# LiPo_Charger.net
KiCad netlist of a schematic drawn in Altium Designer
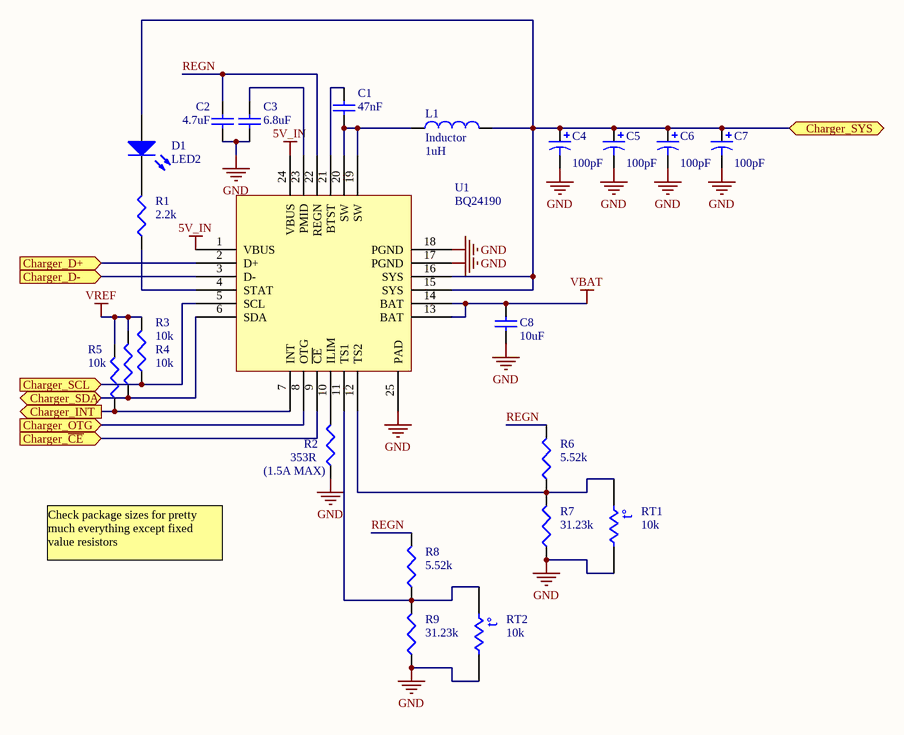
[diagram p0: LiPo_Charger.SchDoc]

(export (version "E")
  (design (tool "Eeschema 10.0.6"))
  (components
    (comp (ref "C1")
      (value "47nF")
      (footprint "1608[0603]")
      (description "Capacitor (Semiconductor SIM Model)")
      (fields (field (name "Comment") "Cap Semi") (field (name "PUBLISHER") "Altium Limited"))
      (libsource (lib "Miscellaneous Devices") (part "Cap Semi"))
    )
    (comp (ref "C2")
      (value "4.7uF")
      (footprint "1608[0603]")
      (description "Capacitor (Semiconductor SIM Model)")
      (fields (field (name "Comment") "Cap Semi") (field (name "PUBLISHER") "Altium Limited"))
      (libsource (lib "Miscellaneous Devices") (part "Cap Semi"))
    )
    (comp (ref "C3")
      (value "6.8uF")
      (footprint "1608[0603]")
      (description "Capacitor (Semiconductor SIM Model)")
      (fields (field (name "Comment") "Cap Semi") (field (name "PUBLISHER") "Altium Limited"))
      (libsource (lib "Miscellaneous Devices") (part "Cap Semi"))
    )
    (comp (ref "C4")
      (value "100pF")
      (footprint "C0805")
      (description "Polarized Capacitor (Surface Mount)")
      (fields (field (name "Comment") "Cap Pol3") (field (name "PUBLISHER") "Altium Limited"))
      (libsource (lib "Miscellaneous Devices") (part "Cap Pol3"))
    )
    (comp (ref "C5")
      (value "100pF")
      (footprint "C0805")
      (description "Polarized Capacitor (Surface Mount)")
      (fields (field (name "Comment") "Cap Pol3") (field (name "PUBLISHER") "Altium Limited"))
      (libsource (lib "Miscellaneous Devices") (part "Cap Pol3"))
    )
    (comp (ref "C6")
      (value "100pF")
      (footprint "C0805")
      (description "Polarized Capacitor (Surface Mount)")
      (fields (field (name "Comment") "Cap Pol3") (field (name "PUBLISHER") "Altium Limited"))
      (libsource (lib "Miscellaneous Devices") (part "Cap Pol3"))
    )
    (comp (ref "C7")
      (value "100pF")
      (footprint "C0805")
      (description "Polarized Capacitor (Surface Mount)")
      (fields (field (name "Comment") "Cap Pol3") (field (name "PUBLISHER") "Altium Limited"))
      (libsource (lib "Miscellaneous Devices") (part "Cap Pol3"))
    )
    (comp (ref "C8")
      (value "10uF")
      (footprint "1608[0603]")
      (description "Capacitor (Semiconductor SIM Model)")
      (fields (field (name "Comment") "Cap Semi") (field (name "PUBLISHER") "Altium Limited"))
      (libsource (lib "Miscellaneous Devices") (part "Cap Semi"))
    )
    (comp (ref "D1")
      (value "LED2")
      (footprint "3.2X1.6X1.1")
      (description "Typical RED, GREEN, YELLOW, AMBER GaAs LED")
      (fields (field (name "PUBLISHER") "Altium Limited"))
      (libsource (lib "Miscellaneous Devices") (part "LED2"))
    )
    (comp (ref "L1")
      (value "Inductor")
      (footprint "0603")
      (fields (field (name "ALTIUM_VALUE") "1uH") (field (name "PUBLISHER") "Altium Limited"))
      (libsource (lib "Miscellaneous Devices") (part "Inductor"))
    )
    (comp (ref "R1")
      (value "2.2k")
      (footprint "J1-0603")
      (description "Resistor")
      (fields (field (name "Comment") "Res3") (field (name "PUBLISHER") "Altium Limited"))
      (libsource (lib "Miscellaneous Devices") (part "Res3"))
    )
    (comp (ref "R2")
      (value "(1.5A MAX)")
      (footprint "J1-0603")
      (description "Resistor")
      (fields (field (name "ALTIUM_VALUE") "353R") (field (name "PUBLISHER") "Altium Limited"))
      (libsource (lib "Miscellaneous Devices") (part "Res3"))
    )
    (comp (ref "R3")
      (value "10k")
      (footprint "J1-0603")
      (description "Resistor")
      (fields (field (name "PUBLISHER") "Altium Limited"))
      (libsource (lib "Miscellaneous Devices") (part "Res3"))
    )
    (comp (ref "R4")
      (value "10k")
      (footprint "J1-0603")
      (description "Resistor")
      (fields (field (name "PUBLISHER") "Altium Limited"))
      (libsource (lib "Miscellaneous Devices") (part "Res3"))
    )
    (comp (ref "R5")
      (value "10k")
      (footprint "J1-0603")
      (description "Resistor")
      (fields (field (name "PUBLISHER") "Altium Limited"))
      (libsource (lib "Miscellaneous Devices") (part "Res3"))
    )
    (comp (ref "R6")
      (value "5.52k")
      (footprint "J1-0603")
      (description "Resistor")
      (fields (field (name "Comment") "Res3") (field (name "PUBLISHER") "Altium Limited"))
      (libsource (lib "Miscellaneous Devices") (part "Res3"))
    )
    (comp (ref "R7")
      (value "31.23k")
      (footprint "J1-0603")
      (description "Resistor")
      (fields (field (name "Comment") "Res3") (field (name "PUBLISHER") "Altium Limited"))
      (libsource (lib "Miscellaneous Devices") (part "Res3"))
    )
    (comp (ref "R8")
      (value "5.52k")
      (footprint "J1-0603")
      (description "Resistor")
      (fields (field (name "Comment") "Res3") (field (name "PUBLISHER") "Altium Limited"))
      (libsource (lib "Miscellaneous Devices") (part "Res3"))
    )
    (comp (ref "R9")
      (value "31.23k")
      (footprint "J1-0603")
      (description "Resistor")
      (fields (field (name "Comment") "Res3") (field (name "PUBLISHER") "Altium Limited"))
      (libsource (lib "Miscellaneous Devices") (part "Res3"))
    )
    (comp (ref "RT1")
      (value "10k")
      (footprint "6-0805_N")
      (description "Thermistor")
      (fields (field (name "Comment") "Res Thermal") (field (name "PUBLISHER") "Altium Limited"))
      (libsource (lib "Miscellaneous Devices") (part "Res Thermal"))
    )
    (comp (ref "RT2")
      (value "10k")
      (footprint "6-0805_N")
      (description "Thermistor")
      (fields (field (name "Comment") "Res Thermal") (field (name "PUBLISHER") "Altium Limited"))
      (libsource (lib "Miscellaneous Devices") (part "Res Thermal"))
    )
    (comp (ref "U1")
      (value "BQ24190")
      (footprint "QFN50P400X400-24V9L")
      (description "I2C Controlled 4.5A Single Cell LiPo Charger w/ USB")
      (libsource (lib "Power_Component_Symbols") (part "BQ24190"))
    )
  )
  (nets
    (net (code "1") (name "/Charger_D+") (class "Default")
      (node (ref "U1") (pin "2") (pinfunction "D+_2") (pintype "passive"))
    )
    (net (code "2") (name "/Charger_D-") (class "Default")
      (node (ref "U1") (pin "3") (pinfunction "D-_3") (pintype "passive"))
    )
    (net (code "3") (name "/Charger_INT") (class "Default")
      (node (ref "R5") (pin "1") (pinfunction "1_1") (pintype "passive"))
      (node (ref "U1") (pin "7") (pinfunction "INT_7") (pintype "passive"))
    )
    (net (code "4") (name "/Charger_OTG") (class "Default")
      (node (ref "U1") (pin "8") (pinfunction "OTG_8") (pintype "passive"))
    )
    (net (code "5") (name "/Charger_SCL") (class "Default")
      (node (ref "R3") (pin "1") (pinfunction "1_1") (pintype "passive"))
      (node (ref "U1") (pin "5") (pinfunction "SCL_5") (pintype "passive"))
    )
    (net (code "6") (name "/Charger_SDA") (class "Default")
      (node (ref "R4") (pin "1") (pinfunction "1_1") (pintype "passive"))
      (node (ref "U1") (pin "6") (pinfunction "SDA_6") (pintype "passive"))
    )
    (net (code "7") (name "/Charger_SYS") (class "Default")
      (node (ref "C4") (pin "1") (pinfunction "1_1") (pintype "passive"))
      (node (ref "C5") (pin "1") (pinfunction "1_1") (pintype "passive"))
      (node (ref "C6") (pin "1") (pinfunction "1_1") (pintype "passive"))
      (node (ref "C7") (pin "1") (pinfunction "1_1") (pintype "passive"))
      (node (ref "D1") (pin "1") (pinfunction "A_1") (pintype "passive"))
      (node (ref "L1") (pin "2") (pinfunction "2_2") (pintype "passive"))
      (node (ref "U1") (pin "15") (pinfunction "SYS_15") (pintype "power_in"))
      (node (ref "U1") (pin "16") (pinfunction "SYS_16") (pintype "power_in"))
    )
    (net (code "8") (name "/Charger_~{CE}") (class "Default")
      (node (ref "U1") (pin "9") (pinfunction "~{CE}_9") (pintype "passive"))
    )
    (net (code "9") (name "/REGN") (class "Default")
      (node (ref "C2") (pin "2") (pinfunction "2_2") (pintype "passive"))
      (node (ref "R6") (pin "2") (pinfunction "2_2") (pintype "passive"))
      (node (ref "R8") (pin "2") (pinfunction "2_2") (pintype "passive"))
      (node (ref "U1") (pin "22") (pinfunction "REGN_22") (pintype "passive"))
    )
    (net (code "10") (name "5V_IN") (class "Default")
      (node (ref "U1") (pin "1") (pinfunction "VBUS_1") (pintype "power_in"))
      (node (ref "U1") (pin "24") (pinfunction "VBUS_24") (pintype "power_in"))
    )
    (net (code "11") (name "GND") (class "Default")
      (node (ref "C2") (pin "1") (pinfunction "1_1") (pintype "passive"))
      (node (ref "C3") (pin "1") (pinfunction "1_1") (pintype "passive"))
      (node (ref "C4") (pin "2") (pinfunction "2_2") (pintype "passive"))
      (node (ref "C5") (pin "2") (pinfunction "2_2") (pintype "passive"))
      (node (ref "C6") (pin "2") (pinfunction "2_2") (pintype "passive"))
      (node (ref "C7") (pin "2") (pinfunction "2_2") (pintype "passive"))
      (node (ref "C8") (pin "2") (pinfunction "2_2") (pintype "passive"))
      (node (ref "R2") (pin "1") (pinfunction "1_1") (pintype "passive"))
      (node (ref "R7") (pin "1") (pinfunction "1_1") (pintype "passive"))
      (node (ref "R9") (pin "1") (pinfunction "1_1") (pintype "passive"))
      (node (ref "RT1") (pin "2") (pinfunction "2_2") (pintype "passive"))
      (node (ref "RT2") (pin "2") (pinfunction "2_2") (pintype "passive"))
      (node (ref "U1") (pin "17") (pinfunction "PGND_17") (pintype "power_in"))
      (node (ref "U1") (pin "18") (pinfunction "PGND_18") (pintype "power_in"))
      (node (ref "U1") (pin "25") (pinfunction "PAD_25") (pintype "power_in"))
    )
    (net (code "12") (name "Net-(C1-Pad1)") (class "Default")
      (node (ref "C1") (pin "1") (pinfunction "1_1") (pintype "passive"))
      (node (ref "L1") (pin "1") (pinfunction "1_1") (pintype "passive"))
      (node (ref "U1") (pin "19") (pinfunction "SW_19") (pintype "passive"))
      (node (ref "U1") (pin "20") (pinfunction "SW_20") (pintype "passive"))
    )
    (net (code "13") (name "Net-(D1-K)") (class "Default")
      (node (ref "D1") (pin "2") (pinfunction "K_2") (pintype "passive"))
      (node (ref "R1") (pin "2") (pinfunction "2_2") (pintype "passive"))
    )
    (net (code "14") (name "Net-(U1-BTST)") (class "Default")
      (node (ref "C1") (pin "2") (pinfunction "2_2") (pintype "passive"))
      (node (ref "U1") (pin "21") (pinfunction "BTST_21") (pintype "passive"))
    )
    (net (code "15") (name "Net-(U1-ILIM)") (class "Default")
      (node (ref "R2") (pin "2") (pinfunction "2_2") (pintype "passive"))
      (node (ref "U1") (pin "10") (pinfunction "ILIM_10") (pintype "passive"))
    )
    (net (code "16") (name "Net-(U1-PMID)") (class "Default")
      (node (ref "C3") (pin "2") (pinfunction "2_2") (pintype "passive"))
      (node (ref "U1") (pin "23") (pinfunction "PMID_23") (pintype "passive"))
    )
    (net (code "17") (name "Net-(U1-STAT)") (class "Default")
      (node (ref "R1") (pin "1") (pinfunction "1_1") (pintype "passive"))
      (node (ref "U1") (pin "4") (pinfunction "STAT_4") (pintype "passive"))
    )
    (net (code "18") (name "Net-(U1-TS1)") (class "Default")
      (node (ref "R8") (pin "1") (pinfunction "1_1") (pintype "passive"))
      (node (ref "R9") (pin "2") (pinfunction "2_2") (pintype "passive"))
      (node (ref "RT2") (pin "1") (pinfunction "1_1") (pintype "passive"))
      (node (ref "U1") (pin "11") (pinfunction "TS1_11") (pintype "passive"))
    )
    (net (code "19") (name "Net-(U1-TS2)") (class "Default")
      (node (ref "R6") (pin "1") (pinfunction "1_1") (pintype "passive"))
      (node (ref "R7") (pin "2") (pinfunction "2_2") (pintype "passive"))
      (node (ref "RT1") (pin "1") (pinfunction "1_1") (pintype "passive"))
      (node (ref "U1") (pin "12") (pinfunction "TS2_12") (pintype "passive"))
    )
    (net (code "20") (name "VBAT") (class "Default")
      (node (ref "C8") (pin "1") (pinfunction "1_1") (pintype "passive"))
      (node (ref "U1") (pin "13") (pinfunction "BAT_13") (pintype "power_in"))
      (node (ref "U1") (pin "14") (pinfunction "BAT_14") (pintype "power_in"))
    )
    (net (code "21") (name "VREF") (class "Default")
      (node (ref "R3") (pin "2") (pinfunction "2_2") (pintype "passive"))
      (node (ref "R4") (pin "2") (pinfunction "2_2") (pintype "passive"))
      (node (ref "R5") (pin "2") (pinfunction "2_2") (pintype "passive"))
    )
  )
)
